# power_amp.net
KiCad netlist of a schematic drawn in EAGLE
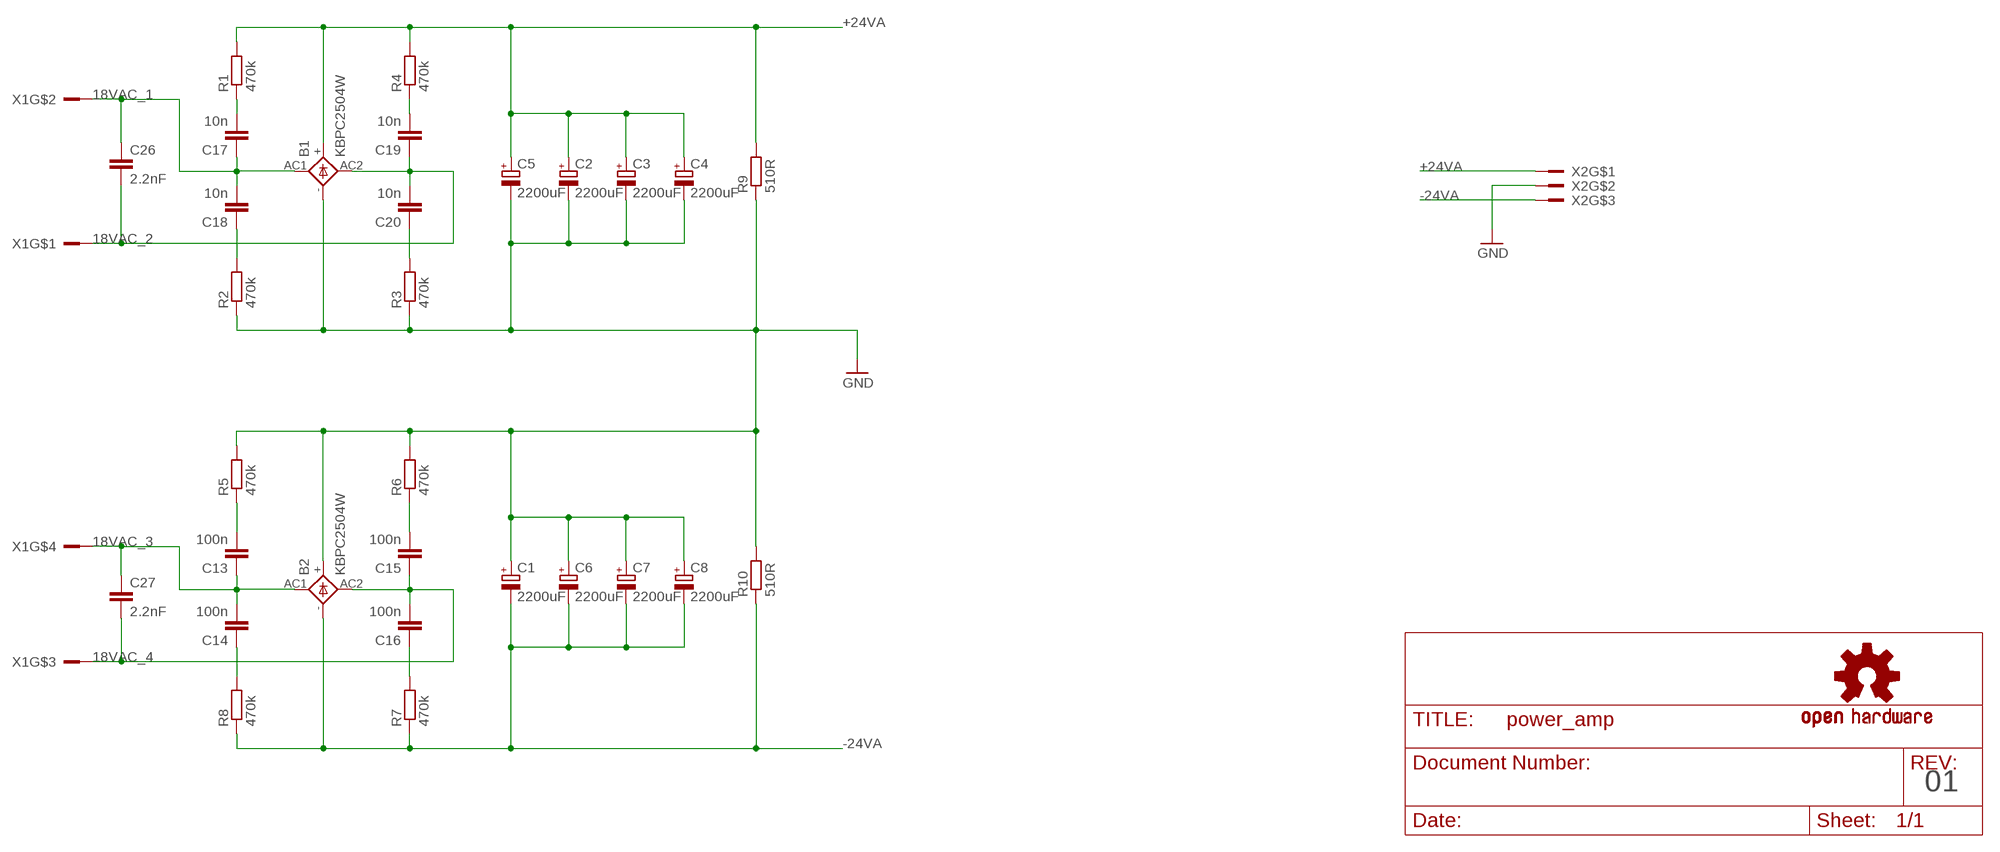
[diagram p0: schematic, sheet 1]

(export (version "E")
  (design (tool "Eeschema 10.0.6"))
  (components
    (comp (ref "B1")
      (value "KBPC2504W")
      (footprint "eagle-import:DC_KBPC")
      (libsource (lib "eagle-import") (part "DC_KBPC"))
    )
    (comp (ref "B2")
      (value "KBPC2504W")
      (footprint "eagle-import:DC_KBPC")
      (libsource (lib "eagle-import") (part "DC_KBPC"))
    )
    (comp (ref "C1")
      (value "2200uF")
      (footprint "eagle-import:E7,5-18")
      (libsource (lib "eagle-import") (part "CPOL-EUE7.5-18"))
    )
    (comp (ref "C2")
      (value "2200uF")
      (footprint "eagle-import:E7,5-18")
      (libsource (lib "eagle-import") (part "CPOL-EUE7.5-18"))
    )
    (comp (ref "C3")
      (value "2200uF")
      (footprint "eagle-import:E7,5-18")
      (libsource (lib "eagle-import") (part "CPOL-EUE7.5-18"))
    )
    (comp (ref "C4")
      (value "2200uF")
      (footprint "eagle-import:E7,5-18")
      (libsource (lib "eagle-import") (part "CPOL-EUE7.5-18"))
    )
    (comp (ref "C5")
      (value "2200uF")
      (footprint "eagle-import:E7,5-18")
      (libsource (lib "eagle-import") (part "CPOL-EUE7.5-18"))
    )
    (comp (ref "C6")
      (value "2200uF")
      (footprint "eagle-import:E7,5-18")
      (libsource (lib "eagle-import") (part "CPOL-EUE7.5-18"))
    )
    (comp (ref "C7")
      (value "2200uF")
      (footprint "eagle-import:E7,5-18")
      (libsource (lib "eagle-import") (part "CPOL-EUE7.5-18"))
    )
    (comp (ref "C8")
      (value "2200uF")
      (footprint "eagle-import:E7,5-18")
      (libsource (lib "eagle-import") (part "CPOL-EUE7.5-18"))
    )
    (comp (ref "C13")
      (value "100n")
      (footprint "eagle-import:C0805")
      (libsource (lib "eagle-import") (part "C-EUC0805"))
    )
    (comp (ref "C14")
      (value "100n")
      (footprint "eagle-import:C0805")
      (libsource (lib "eagle-import") (part "C-EUC0805"))
    )
    (comp (ref "C15")
      (value "100n")
      (footprint "eagle-import:C0805")
      (libsource (lib "eagle-import") (part "C-EUC0805"))
    )
    (comp (ref "C16")
      (value "100n")
      (footprint "eagle-import:C0805")
      (libsource (lib "eagle-import") (part "C-EUC0805"))
    )
    (comp (ref "C17")
      (value "10n")
      (footprint "eagle-import:C0805")
      (libsource (lib "eagle-import") (part "C-EUC0805"))
    )
    (comp (ref "C18")
      (value "10n")
      (footprint "eagle-import:C0805")
      (libsource (lib "eagle-import") (part "C-EUC0805"))
    )
    (comp (ref "C19")
      (value "10n")
      (footprint "eagle-import:C0805")
      (libsource (lib "eagle-import") (part "C-EUC0805"))
    )
    (comp (ref "C20")
      (value "10n")
      (footprint "eagle-import:C0805")
      (libsource (lib "eagle-import") (part "C-EUC0805"))
    )
    (comp (ref "C26")
      (value "2.2nF")
      (footprint "eagle-import:C5B4.5")
      (libsource (lib "eagle-import") (part "C5/4.5"))
    )
    (comp (ref "C27")
      (value "2.2nF")
      (footprint "eagle-import:C5B4.5")
      (libsource (lib "eagle-import") (part "C5/4.5"))
    )
    (comp (ref "R1")
      (value "470k")
      (footprint "eagle-import:R0805W")
      (libsource (lib "eagle-import") (part "R-EU_R0805W"))
    )
    (comp (ref "R2")
      (value "470k")
      (footprint "eagle-import:R0805W")
      (libsource (lib "eagle-import") (part "R-EU_R0805W"))
    )
    (comp (ref "R3")
      (value "470k")
      (footprint "eagle-import:R0805W")
      (libsource (lib "eagle-import") (part "R-EU_R0805W"))
    )
    (comp (ref "R4")
      (value "470k")
      (footprint "eagle-import:R0805W")
      (libsource (lib "eagle-import") (part "R-EU_R0805W"))
    )
    (comp (ref "R5")
      (value "470k")
      (footprint "eagle-import:R0805W")
      (libsource (lib "eagle-import") (part "R-EU_R0805W"))
    )
    (comp (ref "R6")
      (value "470k")
      (footprint "eagle-import:R0805W")
      (libsource (lib "eagle-import") (part "R-EU_R0805W"))
    )
    (comp (ref "R7")
      (value "470k")
      (footprint "eagle-import:R0805W")
      (libsource (lib "eagle-import") (part "R-EU_R0805W"))
    )
    (comp (ref "R8")
      (value "470k")
      (footprint "eagle-import:R0805W")
      (libsource (lib "eagle-import") (part "R-EU_R0805W"))
    )
    (comp (ref "R9")
      (value "510R")
      (footprint "eagle-import:0922_22")
      (libsource (lib "eagle-import") (part "R-EU_0922/22"))
    )
    (comp (ref "R10")
      (value "510R")
      (footprint "eagle-import:0922_22")
      (libsource (lib "eagle-import") (part "R-EU_0922/22"))
    )
    (comp (ref "U$7")
      (value "OSHW-LOGOM")
      (footprint "eagle-import:OSHW-LOGO-M")
      (libsource (lib "eagle-import") (part "OSHW-LOGOM"))
    )
    (comp (ref "X1")
      (value "DEGSON_4")
      (footprint "eagle-import:DEGSON_4")
      (libsource (lib "eagle-import") (part "DEGSON_4"))
    )
    (comp (ref "X2")
      (value "DEGSON_3")
      (footprint "eagle-import:DEGSON_3")
      (libsource (lib "eagle-import") (part "DEGSON_3"))
    )
  )
  (nets
    (net (code "1") (name "/+24VA") (class "Default")
      (node (ref "B1") (pin "+") (pinfunction "+_+") (pintype "passive"))
      (node (ref "C2") (pin "+") (pinfunction "+_+") (pintype "passive"))
      (node (ref "C3") (pin "+") (pinfunction "+_+") (pintype "passive"))
      (node (ref "C4") (pin "+") (pinfunction "+_+") (pintype "passive"))
      (node (ref "C5") (pin "+") (pinfunction "+_+") (pintype "passive"))
      (node (ref "R1") (pin "2") (pinfunction "2_2") (pintype "passive"))
      (node (ref "R4") (pin "2") (pinfunction "2_2") (pintype "passive"))
      (node (ref "R9") (pin "2") (pinfunction "2_2") (pintype "passive"))
      (node (ref "X2") (pin "1") (pinfunction "KL_1") (pintype "passive"))
    )
    (net (code "2") (name "/-24VA") (class "Default")
      (node (ref "B2") (pin "-") (pinfunction "-_-") (pintype "passive"))
      (node (ref "C1") (pin "-") (pinfunction "-_-") (pintype "passive"))
      (node (ref "C6") (pin "-") (pinfunction "-_-") (pintype "passive"))
      (node (ref "C7") (pin "-") (pinfunction "-_-") (pintype "passive"))
      (node (ref "C8") (pin "-") (pinfunction "-_-") (pintype "passive"))
      (node (ref "R10") (pin "1") (pinfunction "1_1") (pintype "passive"))
      (node (ref "R7") (pin "1") (pinfunction "1_1") (pintype "passive"))
      (node (ref "R8") (pin "1") (pinfunction "1_1") (pintype "passive"))
      (node (ref "X2") (pin "3") (pinfunction "KL_3") (pintype "passive"))
    )
    (net (code "3") (name "/18VAC_1") (class "Default")
      (node (ref "B1") (pin "AC1") (pinfunction "AC1_AC1") (pintype "passive"))
      (node (ref "C17") (pin "1") (pinfunction "1_1") (pintype "passive"))
      (node (ref "C18") (pin "2") (pinfunction "2_2") (pintype "passive"))
      (node (ref "C26") (pin "1") (pinfunction "1_1") (pintype "passive"))
      (node (ref "X1") (pin "2") (pinfunction "KL_2") (pintype "passive"))
    )
    (net (code "4") (name "/18VAC_2") (class "Default")
      (node (ref "B1") (pin "AC2") (pinfunction "AC2_AC2") (pintype "passive"))
      (node (ref "C19") (pin "1") (pinfunction "1_1") (pintype "passive"))
      (node (ref "C20") (pin "2") (pinfunction "2_2") (pintype "passive"))
      (node (ref "C26") (pin "2") (pinfunction "2_2") (pintype "passive"))
      (node (ref "X1") (pin "1") (pinfunction "KL_1") (pintype "passive"))
    )
    (net (code "5") (name "/18VAC_3") (class "Default")
      (node (ref "B2") (pin "AC1") (pinfunction "AC1_AC1") (pintype "passive"))
      (node (ref "C13") (pin "1") (pinfunction "1_1") (pintype "passive"))
      (node (ref "C14") (pin "2") (pinfunction "2_2") (pintype "passive"))
      (node (ref "C27") (pin "1") (pinfunction "1_1") (pintype "passive"))
      (node (ref "X1") (pin "4") (pinfunction "KL_4") (pintype "passive"))
    )
    (net (code "6") (name "/18VAC_4") (class "Default")
      (node (ref "B2") (pin "AC2") (pinfunction "AC2_AC2") (pintype "passive"))
      (node (ref "C15") (pin "1") (pinfunction "1_1") (pintype "passive"))
      (node (ref "C16") (pin "2") (pinfunction "2_2") (pintype "passive"))
      (node (ref "C27") (pin "2") (pinfunction "2_2") (pintype "passive"))
      (node (ref "X1") (pin "3") (pinfunction "KL_3") (pintype "passive"))
    )
    (net (code "7") (name "GND") (class "Default")
      (node (ref "B1") (pin "-") (pinfunction "-_-") (pintype "passive"))
      (node (ref "B2") (pin "+") (pinfunction "+_+") (pintype "passive"))
      (node (ref "C1") (pin "+") (pinfunction "+_+") (pintype "passive"))
      (node (ref "C2") (pin "-") (pinfunction "-_-") (pintype "passive"))
      (node (ref "C3") (pin "-") (pinfunction "-_-") (pintype "passive"))
      (node (ref "C4") (pin "-") (pinfunction "-_-") (pintype "passive"))
      (node (ref "C5") (pin "-") (pinfunction "-_-") (pintype "passive"))
      (node (ref "C6") (pin "+") (pinfunction "+_+") (pintype "passive"))
      (node (ref "C7") (pin "+") (pinfunction "+_+") (pintype "passive"))
      (node (ref "C8") (pin "+") (pinfunction "+_+") (pintype "passive"))
      (node (ref "R10") (pin "2") (pinfunction "2_2") (pintype "passive"))
      (node (ref "R2") (pin "1") (pinfunction "1_1") (pintype "passive"))
      (node (ref "R3") (pin "1") (pinfunction "1_1") (pintype "passive"))
      (node (ref "R5") (pin "2") (pinfunction "2_2") (pintype "passive"))
      (node (ref "R6") (pin "2") (pinfunction "2_2") (pintype "passive"))
      (node (ref "R9") (pin "1") (pinfunction "1_1") (pintype "passive"))
      (node (ref "X2") (pin "2") (pinfunction "KL_2") (pintype "passive"))
    )
    (net (code "8") (name "Net-(C13-Pad2)") (class "Default")
      (node (ref "C13") (pin "2") (pinfunction "2_2") (pintype "passive"))
      (node (ref "R5") (pin "1") (pinfunction "1_1") (pintype "passive"))
    )
    (net (code "9") (name "Net-(C14-Pad1)") (class "Default")
      (node (ref "C14") (pin "1") (pinfunction "1_1") (pintype "passive"))
      (node (ref "R8") (pin "2") (pinfunction "2_2") (pintype "passive"))
    )
    (net (code "10") (name "Net-(C15-Pad2)") (class "Default")
      (node (ref "C15") (pin "2") (pinfunction "2_2") (pintype "passive"))
      (node (ref "R6") (pin "1") (pinfunction "1_1") (pintype "passive"))
    )
    (net (code "11") (name "Net-(C16-Pad1)") (class "Default")
      (node (ref "C16") (pin "1") (pinfunction "1_1") (pintype "passive"))
      (node (ref "R7") (pin "2") (pinfunction "2_2") (pintype "passive"))
    )
    (net (code "12") (name "Net-(C17-Pad2)") (class "Default")
      (node (ref "C17") (pin "2") (pinfunction "2_2") (pintype "passive"))
      (node (ref "R1") (pin "1") (pinfunction "1_1") (pintype "passive"))
    )
    (net (code "13") (name "Net-(C18-Pad1)") (class "Default")
      (node (ref "C18") (pin "1") (pinfunction "1_1") (pintype "passive"))
      (node (ref "R2") (pin "2") (pinfunction "2_2") (pintype "passive"))
    )
    (net (code "14") (name "Net-(C19-Pad2)") (class "Default")
      (node (ref "C19") (pin "2") (pinfunction "2_2") (pintype "passive"))
      (node (ref "R4") (pin "1") (pinfunction "1_1") (pintype "passive"))
    )
    (net (code "15") (name "Net-(C20-Pad1)") (class "Default")
      (node (ref "C20") (pin "1") (pinfunction "1_1") (pintype "passive"))
      (node (ref "R3") (pin "2") (pinfunction "2_2") (pintype "passive"))
    )
  )
)
